# JS7628_base_audio_v1_0.net
KiCad netlist of a schematic drawn in Altium Designer
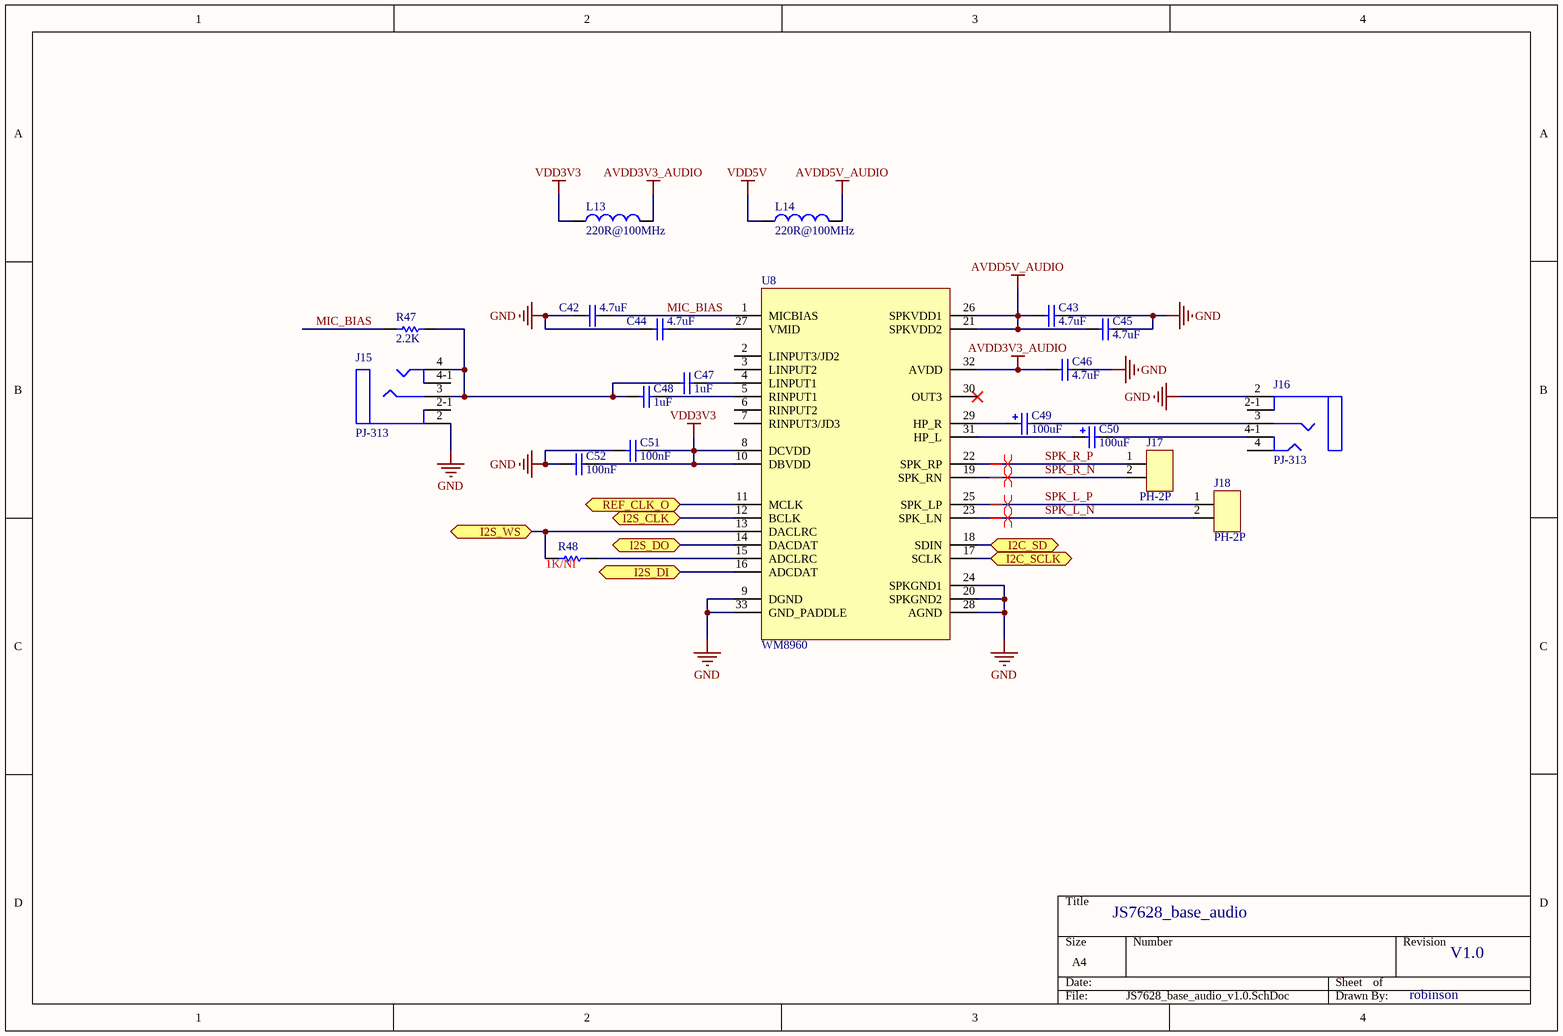
[diagram p0: JS7628_base_audio_v1.0.SchDoc]

(export (version "E")
  (design (tool "Eeschema 10.0.6"))
  (components
    (comp (ref "C42")
      (value "4.7uF")
      (footprint "0603")
      (fields (field (name "Comment") "CAP-SMT"))
      (libsource (lib "MyMiscellaneousDevice") (part "CAP-SMT"))
    )
    (comp (ref "C43")
      (value "4.7uF")
      (footprint "0603")
      (fields (field (name "Comment") "CAP-SMT"))
      (libsource (lib "MyMiscellaneousDevice") (part "CAP-SMT"))
    )
    (comp (ref "C44")
      (value "4.7uF")
      (footprint "0603")
      (fields (field (name "Comment") "CAP-SMT"))
      (libsource (lib "MyMiscellaneousDevice") (part "CAP-SMT"))
    )
    (comp (ref "C45")
      (value "4.7uF")
      (footprint "0603")
      (fields (field (name "Comment") "CAP-SMT"))
      (libsource (lib "MyMiscellaneousDevice") (part "CAP-SMT"))
    )
    (comp (ref "C46")
      (value "4.7uF")
      (footprint "0603")
      (fields (field (name "Comment") "CAP-SMT"))
      (libsource (lib "MyMiscellaneousDevice") (part "CAP-SMT"))
    )
    (comp (ref "C47")
      (value "1uF")
      (footprint "0603")
      (fields (field (name "Comment") "CAP-SMT"))
      (libsource (lib "MyMiscellaneousDevice") (part "CAP-SMT"))
    )
    (comp (ref "C48")
      (value "1uF")
      (footprint "0603")
      (fields (field (name "Comment") "CAP-SMT"))
      (libsource (lib "MyMiscellaneousDevice") (part "CAP-SMT"))
    )
    (comp (ref "C49")
      (value "100uF")
      (footprint "RB2.5-6.5")
      (fields (field (name "Comment") "cap-pol"))
      (libsource (lib "MyMiscellaneousDevice") (part "cap-pol"))
    )
    (comp (ref "C50")
      (value "100uF")
      (footprint "RB2.5-6.5")
      (fields (field (name "Comment") "cap-pol"))
      (libsource (lib "MyMiscellaneousDevice") (part "cap-pol"))
    )
    (comp (ref "C51")
      (value "100nF")
      (footprint "0603")
      (fields (field (name "Comment") "CAP-SMT"))
      (libsource (lib "MyMiscellaneousDevice") (part "CAP-SMT"))
    )
    (comp (ref "C52")
      (value "100nF")
      (footprint "0603")
      (fields (field (name "Comment") "CAP-SMT"))
      (libsource (lib "MyMiscellaneousDevice") (part "CAP-SMT"))
    )
    (comp (ref "J15")
      (value "PJ-313")
      (footprint "MyMiscellaneousConnector:PJ-313")
      (libsource (lib "MyMiscellaneousConnector") (part "PJ-313"))
    )
    (comp (ref "J16")
      (value "PJ-313")
      (footprint "MyMiscellaneousConnector:PJ-313")
      (libsource (lib "MyMiscellaneousConnector") (part "PJ-313"))
    )
    (comp (ref "J17")
      (value "PH-2P")
      (footprint "MyMiscellaneousConnector:PH2.0-2P")
      (libsource (lib "MyMiscellaneousConnector") (part "PH-2P"))
    )
    (comp (ref "J18")
      (value "PH-2P")
      (footprint "MyMiscellaneousConnector:PH2.0-2P")
      (libsource (lib "MyMiscellaneousConnector") (part "PH-2P"))
    )
    (comp (ref "L13")
      (value "220R@100MHz")
      (footprint "0603")
      (fields (field (name "Comment") "inductor"))
      (libsource (lib "MyMiscellaneousDevice") (part "inductor"))
    )
    (comp (ref "L14")
      (value "220R@100MHz")
      (footprint "0603")
      (fields (field (name "Comment") "inductor"))
      (libsource (lib "MyMiscellaneousDevice") (part "inductor"))
    )
    (comp (ref "R47")
      (value "2.2K")
      (footprint "0603")
      (fields (field (name "Comment") "RES-SMT"))
      (libsource (lib "MyMiscellaneousDevice") (part "RES-SMT"))
    )
    (comp (ref "R48")
      (value "1K/NI")
      (footprint "0603")
      (fields (field (name "Comment") "RES-SMT"))
      (libsource (lib "MyMiscellaneousDevice") (part "RES-SMT"))
    )
    (comp (ref "U8")
      (value "WM8960")
      (footprint "MyMiscellaneousDevice:QFN-32")
      (libsource (lib "MyMiscellaneousDevice") (part "WM8960"))
    )
  )
  (nets
    (net (code "1") (name "/I2C_SCLK") (class "Default")
      (node (ref "U8") (pin "17") (pinfunction "SCLK_17") (pintype "passive"))
    )
    (net (code "2") (name "/I2C_SD") (class "Default")
      (node (ref "U8") (pin "18") (pinfunction "SDIN_18") (pintype "passive"))
    )
    (net (code "3") (name "/I2S_CLK") (class "Default")
      (node (ref "U8") (pin "12") (pinfunction "BCLK_12") (pintype "passive"))
    )
    (net (code "4") (name "/I2S_DI") (class "Default")
      (node (ref "U8") (pin "16") (pinfunction "ADCDAT_16") (pintype "passive"))
    )
    (net (code "5") (name "/I2S_DO") (class "Default")
      (node (ref "U8") (pin "14") (pinfunction "DACDAT_14") (pintype "passive"))
    )
    (net (code "6") (name "/I2S_WS") (class "Default")
      (node (ref "R48") (pin "1") (pinfunction "1_1") (pintype "passive"))
      (node (ref "U8") (pin "13") (pinfunction "DACLRC_13") (pintype "passive"))
    )
    (net (code "7") (name "/MIC_BIAS") (class "Default")
      (node (ref "C42") (pin "1") (pinfunction "1_1") (pintype "passive"))
      (node (ref "R47") (pin "1") (pinfunction "1_1") (pintype "passive"))
      (node (ref "U8") (pin "1") (pinfunction "MICBIAS_1") (pintype "passive"))
    )
    (net (code "8") (name "/REF_CLK_O") (class "Default")
      (node (ref "U8") (pin "11") (pinfunction "MCLK_11") (pintype "passive"))
    )
    (net (code "9") (name "/SPK_L_N") (class "Default")
      (node (ref "J18") (pin "2") (pinfunction "2_2") (pintype "passive"))
      (node (ref "U8") (pin "23") (pinfunction "SPK_LN_23") (pintype "passive"))
    )
    (net (code "10") (name "/SPK_L_P") (class "Default")
      (node (ref "J18") (pin "1") (pinfunction "1_1") (pintype "passive"))
      (node (ref "U8") (pin "25") (pinfunction "SPK_LP_25") (pintype "passive"))
    )
    (net (code "11") (name "/SPK_R_N") (class "Default")
      (node (ref "J17") (pin "2") (pinfunction "2_2") (pintype "passive"))
      (node (ref "U8") (pin "19") (pinfunction "SPK_RN_19") (pintype "passive"))
    )
    (net (code "12") (name "/SPK_R_P") (class "Default")
      (node (ref "J17") (pin "1") (pinfunction "1_1") (pintype "passive"))
      (node (ref "U8") (pin "22") (pinfunction "SPK_RP_22") (pintype "passive"))
    )
    (net (code "13") (name "AVDD3V3_AUDIO") (class "Default")
      (node (ref "C46") (pin "1") (pinfunction "1_1") (pintype "passive"))
      (node (ref "L13") (pin "2") (pinfunction "2_2") (pintype "passive"))
      (node (ref "U8") (pin "32") (pinfunction "AVDD_32") (pintype "passive"))
    )
    (net (code "14") (name "AVDD5V_AUDIO") (class "Default")
      (node (ref "C43") (pin "2") (pinfunction "2_2") (pintype "passive"))
      (node (ref "C45") (pin "2") (pinfunction "2_2") (pintype "passive"))
      (node (ref "L14") (pin "2") (pinfunction "2_2") (pintype "passive"))
      (node (ref "U8") (pin "21") (pinfunction "SPKVDD2_21") (pintype "passive"))
      (node (ref "U8") (pin "26") (pinfunction "SPKVDD1_26") (pintype "passive"))
    )
    (net (code "15") (name "GND") (class "Default")
      (node (ref "C42") (pin "2") (pinfunction "2_2") (pintype "passive"))
      (node (ref "C43") (pin "1") (pinfunction "1_1") (pintype "passive"))
      (node (ref "C44") (pin "2") (pinfunction "2_2") (pintype "passive"))
      (node (ref "C45") (pin "1") (pinfunction "1_1") (pintype "passive"))
      (node (ref "C46") (pin "2") (pinfunction "2_2") (pintype "passive"))
      (node (ref "C51") (pin "1") (pinfunction "1_1") (pintype "passive"))
      (node (ref "C52") (pin "1") (pinfunction "1_1") (pintype "passive"))
      (node (ref "J15") (pin "2") (pinfunction "GND_2") (pintype "passive"))
      (node (ref "J16") (pin "2") (pinfunction "GND_2") (pintype "passive"))
      (node (ref "U8") (pin "20") (pinfunction "SPKGND2_20") (pintype "passive"))
      (node (ref "U8") (pin "24") (pinfunction "SPKGND1_24") (pintype "passive"))
      (node (ref "U8") (pin "28") (pinfunction "AGND_28") (pintype "passive"))
      (node (ref "U8") (pin "33") (pinfunction "GND_PADDLE_33") (pintype "passive"))
      (node (ref "U8") (pin "9") (pinfunction "DGND_9") (pintype "passive"))
    )
    (net (code "16") (name "Net-(C47-Pad1)") (class "Default")
      (node (ref "C47") (pin "1") (pinfunction "1_1") (pintype "passive"))
      (node (ref "C48") (pin "1") (pinfunction "1_1") (pintype "passive"))
      (node (ref "J15") (pin "3") (pintype "passive"))
      (node (ref "J15") (pin "4") (pintype "passive"))
      (node (ref "R47") (pin "2") (pinfunction "2_2") (pintype "passive"))
    )
    (net (code "17") (name "Net-(C49-Pad2)") (class "Default")
      (node (ref "C49") (pin "2") (pinfunction "2_2") (pintype "passive"))
      (node (ref "J16") (pin "3") (pintype "passive"))
    )
    (net (code "18") (name "Net-(C50-Pad2)") (class "Default")
      (node (ref "C50") (pin "2") (pinfunction "2_2") (pintype "passive"))
      (node (ref "J16") (pin "4-1") (pintype "passive"))
    )
    (net (code "19") (name "Net-(U8-ADCLRC)") (class "Default")
      (node (ref "R48") (pin "2") (pinfunction "2_2") (pintype "passive"))
      (node (ref "U8") (pin "15") (pinfunction "ADCLRC_15") (pintype "passive"))
    )
    (net (code "20") (name "Net-(U8-HP_L)") (class "Default")
      (node (ref "C50") (pin "1") (pinfunction "1_1") (pintype "passive"))
      (node (ref "U8") (pin "31") (pinfunction "HP_L_31") (pintype "passive"))
    )
    (net (code "21") (name "Net-(U8-HP_R)") (class "Default")
      (node (ref "C49") (pin "1") (pinfunction "1_1") (pintype "passive"))
      (node (ref "U8") (pin "29") (pinfunction "HP_R_29") (pintype "passive"))
    )
    (net (code "22") (name "Net-(U8-LINPUT1)") (class "Default")
      (node (ref "C47") (pin "2") (pinfunction "2_2") (pintype "passive"))
      (node (ref "U8") (pin "4") (pinfunction "LINPUT1_4") (pintype "passive"))
    )
    (net (code "23") (name "Net-(U8-RINPUT1)") (class "Default")
      (node (ref "C48") (pin "2") (pinfunction "2_2") (pintype "passive"))
      (node (ref "U8") (pin "5") (pinfunction "RINPUT1_5") (pintype "passive"))
    )
    (net (code "24") (name "Net-(U8-VMID)") (class "Default")
      (node (ref "C44") (pin "1") (pinfunction "1_1") (pintype "passive"))
      (node (ref "U8") (pin "27") (pinfunction "VMID_27") (pintype "passive"))
    )
    (net (code "25") (name "VDD3V3") (class "Default")
      (node (ref "C51") (pin "2") (pinfunction "2_2") (pintype "passive"))
      (node (ref "C52") (pin "2") (pinfunction "2_2") (pintype "passive"))
      (node (ref "L13") (pin "1") (pinfunction "1_1") (pintype "passive"))
      (node (ref "U8") (pin "10") (pinfunction "DBVDD_10") (pintype "passive"))
      (node (ref "U8") (pin "8") (pinfunction "DCVDD_8") (pintype "passive"))
    )
    (net (code "26") (name "VDD5V") (class "Default")
      (node (ref "L14") (pin "1") (pinfunction "1_1") (pintype "passive"))
    )
    (net (code "27") (name "unconnected-(J15-Pad2-1)") (class "Default")
      (node (ref "J15") (pin "2-1") (pintype "passive"))
    )
    (net (code "28") (name "unconnected-(J15-Pad4-1)") (class "Default")
      (node (ref "J15") (pin "4-1") (pintype "passive"))
    )
    (net (code "29") (name "unconnected-(J16-Pad2-1)") (class "Default")
      (node (ref "J16") (pin "2-1") (pintype "passive"))
    )
    (net (code "30") (name "unconnected-(J16-Pad4)") (class "Default")
      (node (ref "J16") (pin "4") (pintype "passive"))
    )
    (net (code "31") (name "unconnected-(U8-LINPUT2-Pad3)") (class "Default")
      (node (ref "U8") (pin "3") (pinfunction "LINPUT2_3") (pintype "passive"))
    )
    (net (code "32") (name "unconnected-(U8-LINPUT3{slash}JD2-Pad2)") (class "Default")
      (node (ref "U8") (pin "2") (pinfunction "LINPUT3/JD2_2") (pintype "passive"))
    )
    (net (code "33") (name "unconnected-(U8-OUT3-Pad30)") (class "Default")
      (node (ref "U8") (pin "30") (pinfunction "OUT3_30") (pintype "passive+no_connect"))
    )
    (net (code "34") (name "unconnected-(U8-RINPUT2-Pad6)") (class "Default")
      (node (ref "U8") (pin "6") (pinfunction "RINPUT2_6") (pintype "passive"))
    )
    (net (code "35") (name "unconnected-(U8-RINPUT3{slash}JD3-Pad7)") (class "Default")
      (node (ref "U8") (pin "7") (pinfunction "RINPUT3/JD3_7") (pintype "passive"))
    )
  )
)
